# PowerDriver.net
KiCad netlist of a schematic drawn in Altium Designer
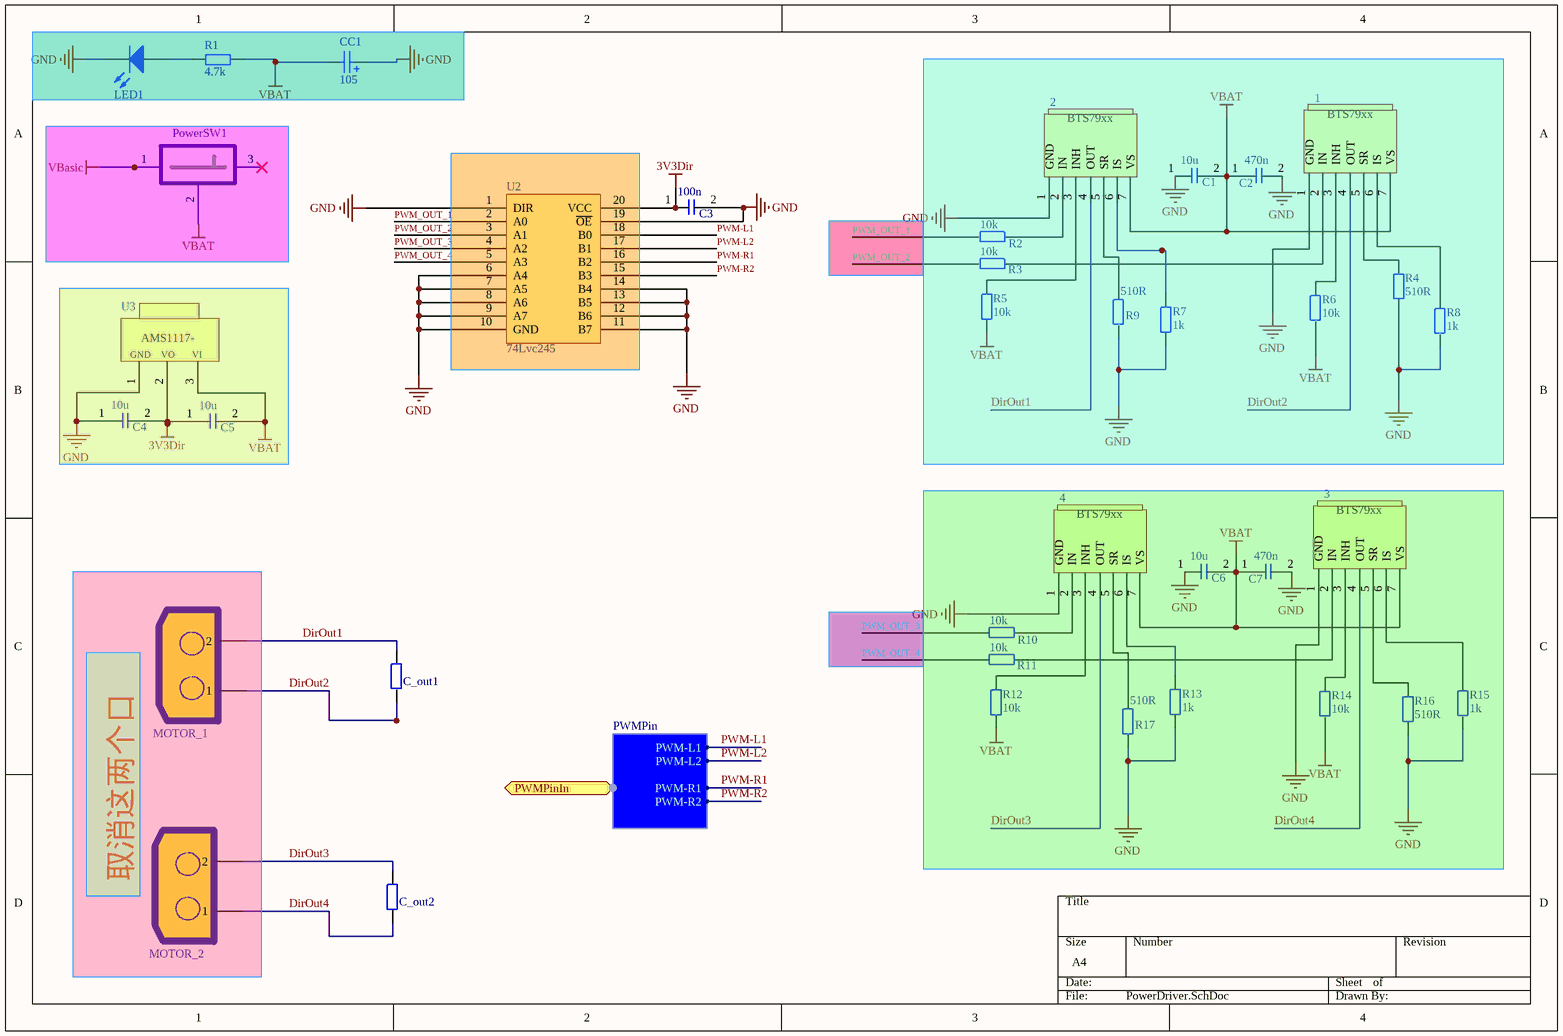
[diagram p0: PowerDriver.SchDoc]

(export (version "E")
  (design (tool "Eeschema 10.0.6"))
  (components
    (comp (ref "1") (value "BTS79xx") (footprint "BTS79xx") (libsource (lib "常用原件库") (part "BTS79xx")))
    (comp (ref "2") (value "BTS79xx") (footprint "BTS79xx") (libsource (lib "常用原件库") (part "BTS79xx")))
    (comp (ref "3") (value "BTS79xx") (footprint "BTS79xx") (libsource (lib "常用原件库") (part "BTS79xx")))
    (comp (ref "4") (value "BTS79xx") (footprint "BTS79xx") (libsource (lib "常用原件库") (part "BTS79xx")))
    (comp (ref "C1") (value "10u") (footprint "0805电容") (libsource (lib "常用原件库") (part "0805电容")))
    (comp (ref "C2") (value "470n") (footprint "0805电容") (libsource (lib "常用原件库") (part "0805电容")))
    (comp (ref "C3") (value "100n") (footprint "0805电容") (libsource (lib "常用原件库") (part "0805电容")))
    (comp (ref "C4") (value "10u") (footprint "0805电容") (libsource (lib "常用原件库") (part "0805电容")))
    (comp (ref "C5") (value "10u") (footprint "0805电容") (libsource (lib "常用原件库") (part "0805电容")))
    (comp (ref "C6") (value "10u") (footprint "0805电容") (libsource (lib "常用原件库") (part "0805电容")))
    (comp (ref "C7") (value "470n") (footprint "0805电容") (libsource (lib "常用原件库") (part "0805电容")))
    (comp (ref "CC1")
      (value "Cap Tan C")
      (footprint "CAPMP6032X26N")
      (description "Polarized Capacitor (Radial)")
      (fields
        (field (name "CAPACITANCE") "105")
        (field (name "VOLTAGE") "16V")
        (field (name "PUBLISHER") "Altium Limited")
      )
      (libsource (lib "ZZCDevice") (part "Cap Tan C"))
    )
    (comp (ref "C_out1") (value "0") (footprint "0805电阻") (libsource (lib "常用原件库") (part "0805电阻")))
    (comp (ref "C_out2") (value "0") (footprint "0805电阻") (libsource (lib "常用原件库") (part "0805电阻")))
    (comp (ref "LED1") (value "0805LED") (footprint "0805LED") (libsource (lib "常用原件库") (part "0805LED")))
    (comp (ref "MOTOR_1") (value "P") (footprint "2脚接头") (libsource (lib "常用原件库") (part "2脚接头")))
    (comp (ref "MOTOR_2") (value "P") (footprint "2脚接头") (libsource (lib "常用原件库") (part "2脚接头")))
    (comp (ref "PowerSW1")
      (value "Power")
      (footprint "PowerSW")
      (libsource (lib "ZZCDevice") (part "PowerSW"))
    )
    (comp (ref "R1") (value "4.7k") (footprint "0805电阻") (libsource (lib "常用原件库") (part "0805电阻")))
    (comp (ref "R2") (value "10k") (footprint "0805电阻") (libsource (lib "常用原件库") (part "0805电阻")))
    (comp (ref "R3") (value "10k") (footprint "0805电阻") (libsource (lib "常用原件库") (part "0805电阻")))
    (comp (ref "R4") (value "510R") (footprint "0805电阻") (libsource (lib "常用原件库") (part "0805电阻")))
    (comp (ref "R5") (value "10k") (footprint "0805电阻") (libsource (lib "常用原件库") (part "0805电阻")))
    (comp (ref "R6") (value "10k") (footprint "0805电阻") (libsource (lib "常用原件库") (part "0805电阻")))
    (comp (ref "R7") (value "1k") (footprint "0805电阻") (libsource (lib "常用原件库") (part "0805电阻")))
    (comp (ref "R8") (value "1k") (footprint "0805电阻") (libsource (lib "常用原件库") (part "0805电阻")))
    (comp (ref "R9") (value "510R") (footprint "0805电阻") (libsource (lib "常用原件库") (part "0805电阻")))
    (comp (ref "R10") (value "10k") (footprint "0805电阻") (libsource (lib "常用原件库") (part "0805电阻")))
    (comp (ref "R11") (value "10k") (footprint "0805电阻") (libsource (lib "常用原件库") (part "0805电阻")))
    (comp (ref "R12") (value "10k") (footprint "0805电阻") (libsource (lib "常用原件库") (part "0805电阻")))
    (comp (ref "R13") (value "1k") (footprint "0805电阻") (libsource (lib "常用原件库") (part "0805电阻")))
    (comp (ref "R14") (value "10k") (footprint "0805电阻") (libsource (lib "常用原件库") (part "0805电阻")))
    (comp (ref "R15") (value "1k") (footprint "0805电阻") (libsource (lib "常用原件库") (part "0805电阻")))
    (comp (ref "R16") (value "510R") (footprint "0805电阻") (libsource (lib "常用原件库") (part "0805电阻")))
    (comp (ref "R17") (value "510R") (footprint "0805电阻") (libsource (lib "常用原件库") (part "0805电阻")))
    (comp (ref "U2")
      (value "74Lvc245")
      (footprint "TSOP65P650X110-20N")
      (libsource (lib "常用原件库") (part "74LVC245"))
    )
    (comp (ref "U3") (value "AMS1117-") (footprint "AMS1117-") (libsource (lib "常用原件库") (part "AMS1117-")))
  )
  (nets
    (net (code "2") (name "/DirOut1") (class "Default")
      (node (ref "2") (pin "4") (pinfunction "OUT_4") (pintype "passive"))
      (node (ref "C_out1") (pin "2") (pinfunction "2_2") (pintype "passive"))
      (node (ref "MOTOR_1") (pin "2") (pinfunction "2_2") (pintype "passive"))
    )
    (net (code "3") (name "/DirOut2") (class "Default")
      (node (ref "1") (pin "4") (pinfunction "OUT_4") (pintype "passive"))
      (node (ref "C_out1") (pin "1") (pinfunction "1_1") (pintype "passive"))
      (node (ref "MOTOR_1") (pin "1") (pinfunction "1_1") (pintype "passive"))
    )
    (net (code "4") (name "/DirOut3") (class "Default")
      (node (ref "4") (pin "4") (pinfunction "OUT_4") (pintype "passive"))
      (node (ref "C_out2") (pin "2") (pinfunction "2_2") (pintype "passive"))
      (node (ref "MOTOR_2") (pin "2") (pinfunction "2_2") (pintype "passive"))
    )
    (net (code "5") (name "/DirOut4") (class "Default")
      (node (ref "3") (pin "4") (pinfunction "OUT_4") (pintype "passive"))
      (node (ref "C_out2") (pin "1") (pinfunction "1_1") (pintype "passive"))
      (node (ref "MOTOR_2") (pin "1") (pinfunction "1_1") (pintype "passive"))
    )
    (net (code "6") (name "/PWM-L1") (class "Default")
      (node (ref "U2") (pin "18") (pinfunction "B0_18") (pintype "passive"))
    )
    (net (code "7") (name "/PWM-L2") (class "Default")
      (node (ref "U2") (pin "17") (pinfunction "B1_17") (pintype "passive"))
    )
    (net (code "8") (name "/PWM-R1") (class "Default")
      (node (ref "U2") (pin "16") (pinfunction "B2_16") (pintype "passive"))
    )
    (net (code "9") (name "/PWM-R2") (class "Default")
      (node (ref "U2") (pin "15") (pinfunction "B3_15") (pintype "passive"))
    )
    (net (code "10") (name "/PWM_OUT_1") (class "Default")
      (node (ref "R2") (pin "1") (pinfunction "1_1") (pintype "passive"))
      (node (ref "U2") (pin "2") (pinfunction "A0_2") (pintype "passive"))
    )
    (net (code "11") (name "/PWM_OUT_2") (class "Default")
      (node (ref "R3") (pin "1") (pinfunction "1_1") (pintype "passive"))
      (node (ref "U2") (pin "3") (pinfunction "A1_3") (pintype "passive"))
    )
    (net (code "12") (name "/PWM_OUT_3") (class "Default")
      (node (ref "R10") (pin "1") (pinfunction "1_1") (pintype "passive"))
      (node (ref "U2") (pin "4") (pinfunction "A2_4") (pintype "passive"))
    )
    (net (code "13") (name "/PWM_OUT_4") (class "Default")
      (node (ref "R11") (pin "1") (pinfunction "1_1") (pintype "passive"))
      (node (ref "U2") (pin "5") (pinfunction "A3_5") (pintype "passive"))
    )
    (net (code "15") (name "3V3Dir") (class "Default")
      (node (ref "C3") (pin "1") (pinfunction "1_1") (pintype "passive"))
      (node (ref "C4") (pin "2") (pinfunction "2_2") (pintype "passive"))
      (node (ref "C5") (pin "1") (pinfunction "1_1") (pintype "passive"))
      (node (ref "U2") (pin "20") (pinfunction "VCC_20") (pintype "passive"))
      (node (ref "U3") (pin "2") (pinfunction "Vout_2") (pintype "passive"))
    )
    (net (code "16") (name "GND") (class "Default")
      (node (ref "1") (pin "1") (pinfunction "GND_1") (pintype "passive"))
      (node (ref "2") (pin "1") (pinfunction "GND_1") (pintype "passive"))
      (node (ref "3") (pin "1") (pinfunction "GND_1") (pintype "passive"))
      (node (ref "4") (pin "1") (pinfunction "GND_1") (pintype "passive"))
      (node (ref "C1") (pin "1") (pinfunction "1_1") (pintype "passive"))
      (node (ref "C2") (pin "2") (pinfunction "2_2") (pintype "passive"))
      (node (ref "C3") (pin "2") (pinfunction "2_2") (pintype "passive"))
      (node (ref "C4") (pin "1") (pinfunction "1_1") (pintype "passive"))
      (node (ref "C6") (pin "1") (pinfunction "1_1") (pintype "passive"))
      (node (ref "C7") (pin "2") (pinfunction "2_2") (pintype "passive"))
      (node (ref "CC1") (pin "2") (pinfunction "1_2") (pintype "passive"))
      (node (ref "LED1") (pin "2") (pinfunction "K_2") (pintype "passive"))
      (node (ref "R13") (pin "1") (pinfunction "1_1") (pintype "passive"))
      (node (ref "R15") (pin "1") (pinfunction "1_1") (pintype "passive"))
      (node (ref "R16") (pin "1") (pinfunction "1_1") (pintype "passive"))
      (node (ref "R17") (pin "1") (pinfunction "1_1") (pintype "passive"))
      (node (ref "R4") (pin "1") (pinfunction "1_1") (pintype "passive"))
      (node (ref "R7") (pin "1") (pinfunction "1_1") (pintype "passive"))
      (node (ref "R8") (pin "1") (pinfunction "1_1") (pintype "passive"))
      (node (ref "R9") (pin "1") (pinfunction "1_1") (pintype "passive"))
      (node (ref "U2") (pin "1") (pinfunction "DIR_1") (pintype "passive"))
      (node (ref "U2") (pin "10") (pinfunction "GND_10") (pintype "passive"))
      (node (ref "U2") (pin "11") (pinfunction "B7_11") (pintype "passive"))
      (node (ref "U2") (pin "12") (pinfunction "B6_12") (pintype "passive"))
      (node (ref "U2") (pin "13") (pinfunction "B5_13") (pintype "passive"))
      (node (ref "U2") (pin "14") (pinfunction "B4_14") (pintype "passive"))
      (node (ref "U2") (pin "19") (pinfunction "~{OE}_19") (pintype "passive"))
      (node (ref "U2") (pin "6") (pinfunction "A4_6") (pintype "passive"))
      (node (ref "U2") (pin "7") (pinfunction "A5_7") (pintype "passive"))
      (node (ref "U2") (pin "8") (pinfunction "A6_8") (pintype "passive"))
      (node (ref "U2") (pin "9") (pinfunction "A7_9") (pintype "passive"))
      (node (ref "U3") (pin "1") (pinfunction "GND_1") (pintype "passive"))
    )
    (net (code "17") (name "Net-(1-IN)") (class "Default")
      (node (ref "1") (pin "2") (pinfunction "IN_2") (pintype "passive"))
      (node (ref "R3") (pin "2") (pinfunction "2_2") (pintype "passive"))
    )
    (net (code "18") (name "Net-(1-INH)") (class "Default")
      (node (ref "1") (pin "3") (pinfunction "INH_3") (pintype "passive"))
      (node (ref "R6") (pin "2") (pinfunction "2_2") (pintype "passive"))
    )
    (net (code "19") (name "Net-(1-IS)") (class "Default")
      (node (ref "1") (pin "6") (pinfunction "IS_6") (pintype "passive"))
      (node (ref "R8") (pin "2") (pinfunction "2_2") (pintype "passive"))
    )
    (net (code "20") (name "Net-(1-SR)") (class "Default")
      (node (ref "1") (pin "5") (pinfunction "SR_5") (pintype "passive"))
      (node (ref "R4") (pin "2") (pinfunction "2_2") (pintype "passive"))
    )
    (net (code "21") (name "Net-(2-IN)") (class "Default")
      (node (ref "2") (pin "2") (pinfunction "IN_2") (pintype "passive"))
      (node (ref "R2") (pin "2") (pinfunction "2_2") (pintype "passive"))
    )
    (net (code "22") (name "Net-(2-INH)") (class "Default")
      (node (ref "2") (pin "3") (pinfunction "INH_3") (pintype "passive"))
      (node (ref "R5") (pin "2") (pinfunction "2_2") (pintype "passive"))
    )
    (net (code "23") (name "Net-(2-IS)") (class "Default")
      (node (ref "2") (pin "6") (pinfunction "IS_6") (pintype "passive"))
      (node (ref "R7") (pin "2") (pinfunction "2_2") (pintype "passive"))
    )
    (net (code "24") (name "Net-(2-SR)") (class "Default")
      (node (ref "2") (pin "5") (pinfunction "SR_5") (pintype "passive"))
      (node (ref "R9") (pin "2") (pinfunction "2_2") (pintype "passive"))
    )
    (net (code "25") (name "Net-(3-IN)") (class "Default")
      (node (ref "3") (pin "2") (pinfunction "IN_2") (pintype "passive"))
      (node (ref "R11") (pin "2") (pinfunction "2_2") (pintype "passive"))
    )
    (net (code "26") (name "Net-(3-INH)") (class "Default")
      (node (ref "3") (pin "3") (pinfunction "INH_3") (pintype "passive"))
      (node (ref "R14") (pin "2") (pinfunction "2_2") (pintype "passive"))
    )
    (net (code "27") (name "Net-(3-IS)") (class "Default")
      (node (ref "3") (pin "6") (pinfunction "IS_6") (pintype "passive"))
      (node (ref "R15") (pin "2") (pinfunction "2_2") (pintype "passive"))
    )
    (net (code "28") (name "Net-(3-SR)") (class "Default")
      (node (ref "3") (pin "5") (pinfunction "SR_5") (pintype "passive"))
      (node (ref "R16") (pin "2") (pinfunction "2_2") (pintype "passive"))
    )
    (net (code "29") (name "Net-(4-IN)") (class "Default")
      (node (ref "4") (pin "2") (pinfunction "IN_2") (pintype "passive"))
      (node (ref "R10") (pin "2") (pinfunction "2_2") (pintype "passive"))
    )
    (net (code "30") (name "Net-(4-INH)") (class "Default")
      (node (ref "4") (pin "3") (pinfunction "INH_3") (pintype "passive"))
      (node (ref "R12") (pin "2") (pinfunction "2_2") (pintype "passive"))
    )
    (net (code "31") (name "Net-(4-IS)") (class "Default")
      (node (ref "4") (pin "6") (pinfunction "IS_6") (pintype "passive"))
      (node (ref "R13") (pin "2") (pinfunction "2_2") (pintype "passive"))
    )
    (net (code "32") (name "Net-(4-SR)") (class "Default")
      (node (ref "4") (pin "5") (pinfunction "SR_5") (pintype "passive"))
      (node (ref "R17") (pin "2") (pinfunction "2_2") (pintype "passive"))
    )
    (net (code "33") (name "Net-(LED1-A)") (class "Default")
      (node (ref "LED1") (pin "1") (pinfunction "A_1") (pintype "passive"))
      (node (ref "R1") (pin "2") (pinfunction "2_2") (pintype "passive"))
    )
    (net (code "34") (name "VBAT") (class "Default")
      (node (ref "1") (pin "7") (pinfunction "VS_7") (pintype "passive"))
      (node (ref "2") (pin "7") (pinfunction "VS_7") (pintype "passive"))
      (node (ref "3") (pin "7") (pinfunction "VS_7") (pintype "passive"))
      (node (ref "4") (pin "7") (pinfunction "VS_7") (pintype "passive"))
      (node (ref "C1") (pin "2") (pinfunction "2_2") (pintype "passive"))
      (node (ref "C2") (pin "1") (pinfunction "1_1") (pintype "passive"))
      (node (ref "C5") (pin "2") (pinfunction "2_2") (pintype "passive"))
      (node (ref "C6") (pin "2") (pinfunction "2_2") (pintype "passive"))
      (node (ref "C7") (pin "1") (pinfunction "1_1") (pintype "passive"))
      (node (ref "CC1") (pin "1") (pinfunction "2_1") (pintype "passive"))
      (node (ref "PowerSW1") (pin "2") (pinfunction "2_2") (pintype "passive"))
      (node (ref "R1") (pin "1") (pinfunction "1_1") (pintype "passive"))
      (node (ref "R12") (pin "1") (pinfunction "1_1") (pintype "passive"))
      (node (ref "R14") (pin "1") (pinfunction "1_1") (pintype "passive"))
      (node (ref "R5") (pin "1") (pinfunction "1_1") (pintype "passive"))
      (node (ref "R6") (pin "1") (pinfunction "1_1") (pintype "passive"))
      (node (ref "U3") (pin "3") (pinfunction "Vin_3") (pintype "passive"))
    )
    (net (code "35") (name "VBasic") (class "Default")
      (node (ref "PowerSW1") (pin "1") (pinfunction "1_1") (pintype "passive"))
    )
    (net (code "36") (name "unconnected-(PowerSW1-Pad3)") (class "Default")
      (node (ref "PowerSW1") (pin "3") (pinfunction "3_3") (pintype "passive+no_connect"))
    )
  )
)
